# PIC18F44K22_KONTROL_KART.net
KiCad netlist of a schematic drawn in EAGLE
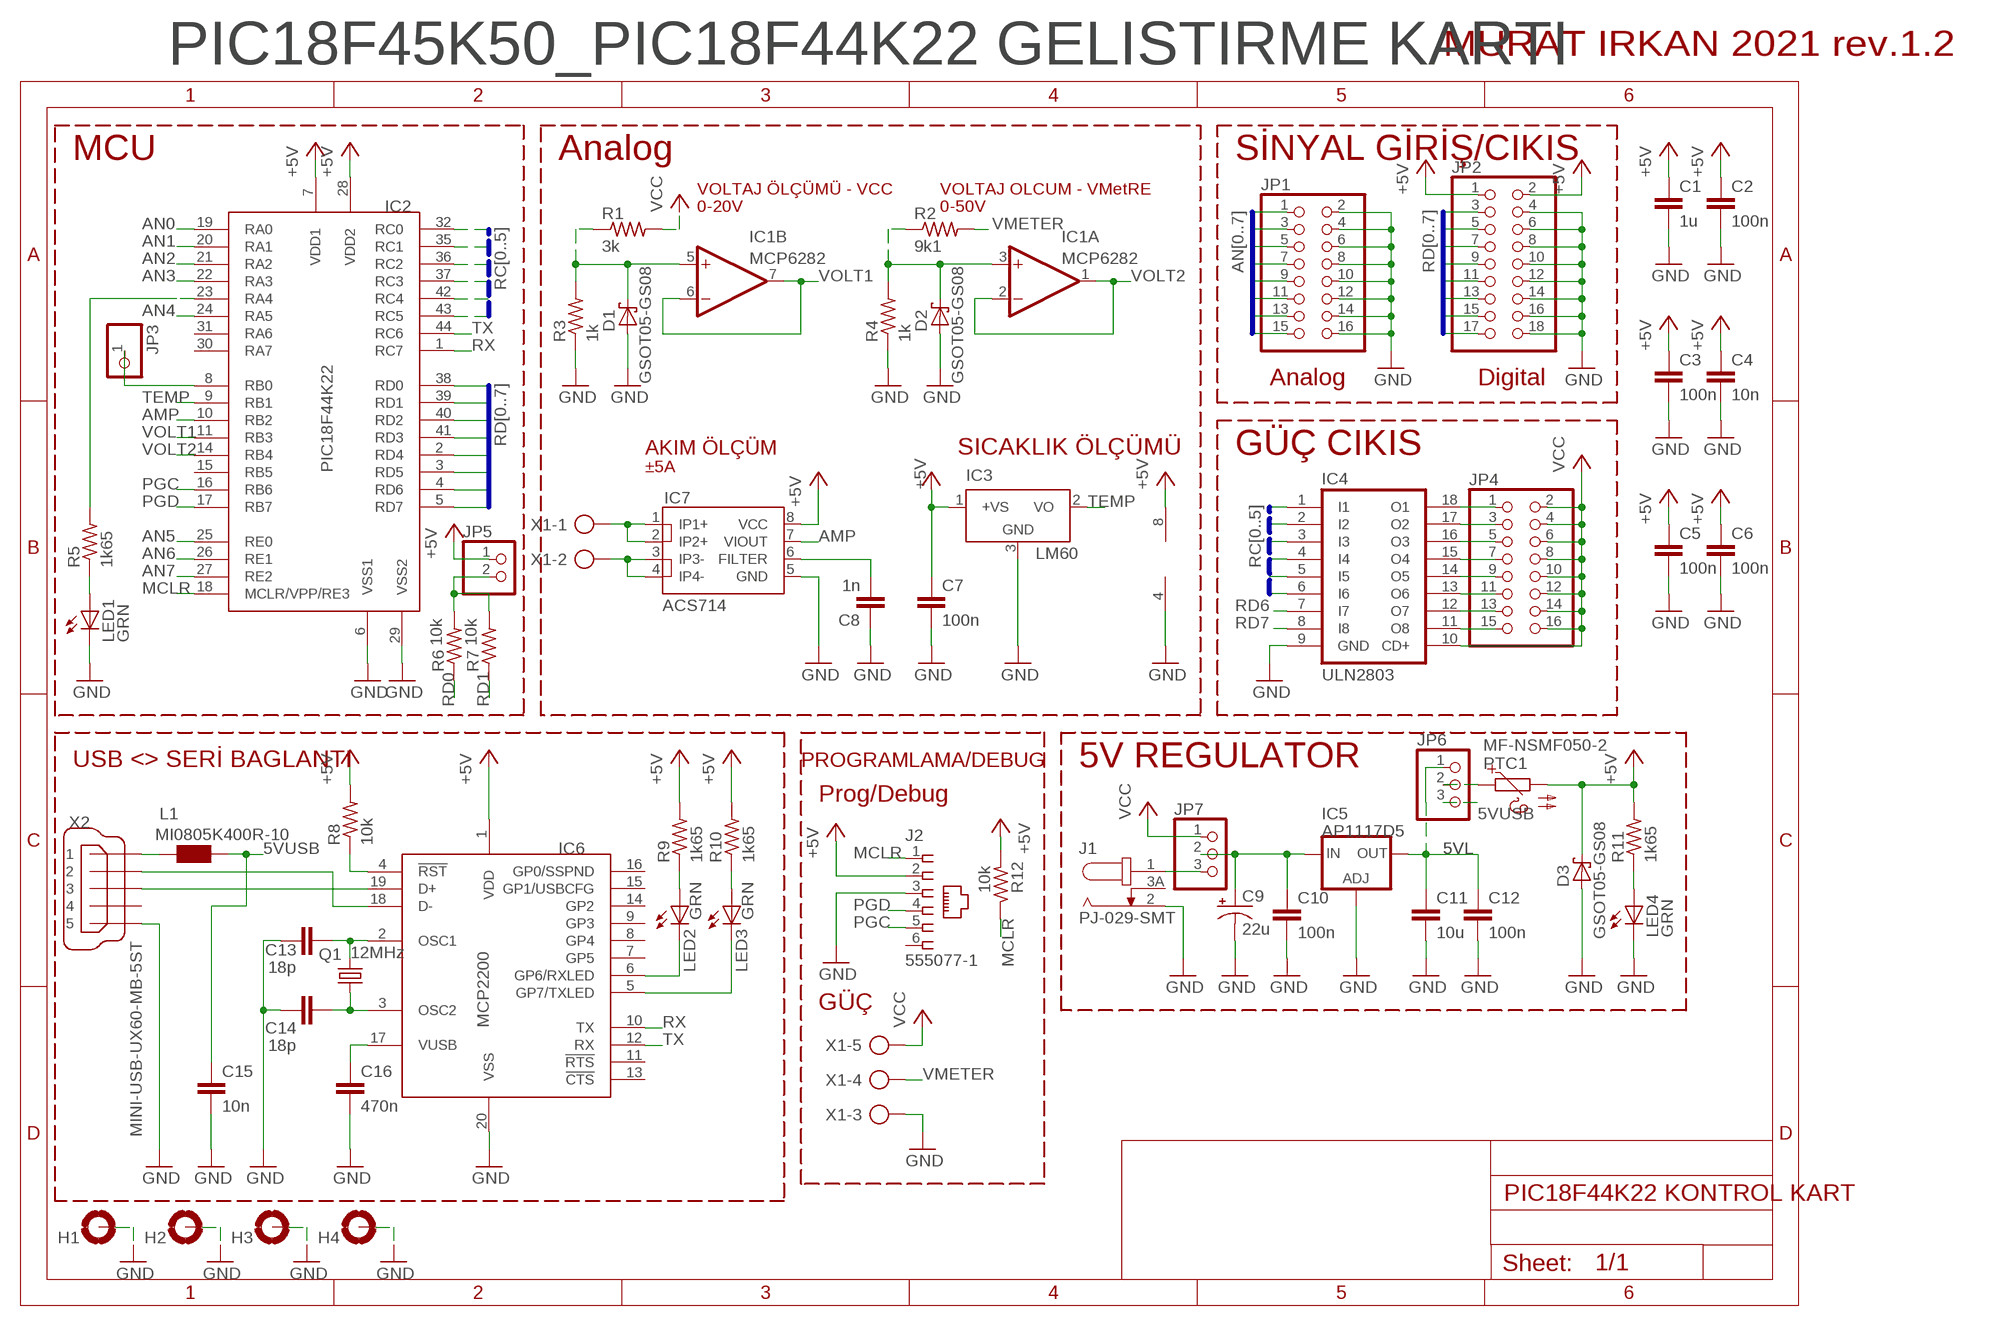
[diagram p0: schematic, sheet 1]

(export (version "E")
  (design (tool "Eeschema 10.0.6"))
  (components
    (comp (ref "C1")
      (value "1u")
      (footprint "eagle-import:C0603")
      (libsource (lib "eagle-import") (part "C-EUC0603"))
    )
    (comp (ref "C2")
      (value "100n")
      (footprint "eagle-import:C0603")
      (libsource (lib "eagle-import") (part "C-EUC0603"))
    )
    (comp (ref "C3")
      (value "100n")
      (footprint "eagle-import:C0603")
      (libsource (lib "eagle-import") (part "C-EUC0603"))
    )
    (comp (ref "C4")
      (value "10n")
      (footprint "eagle-import:C0603")
      (libsource (lib "eagle-import") (part "C-EUC0603"))
    )
    (comp (ref "C5")
      (value "100n")
      (footprint "eagle-import:C0603")
      (libsource (lib "eagle-import") (part "C-EUC0603"))
    )
    (comp (ref "C6")
      (value "100n")
      (footprint "eagle-import:C0603")
      (libsource (lib "eagle-import") (part "C-EUC0603"))
    )
    (comp (ref "C7")
      (value "100n")
      (footprint "eagle-import:C0603")
      (libsource (lib "eagle-import") (part "C-EUC0603"))
    )
    (comp (ref "C8")
      (value "1n")
      (footprint "eagle-import:C0603")
      (libsource (lib "eagle-import") (part "C-EUC0603"))
    )
    (comp (ref "C9")
      (value "22u")
      (footprint "eagle-import:153CLV-0505")
      (libsource (lib "eagle-import") (part "CPOL-US153CLV-0505"))
    )
    (comp (ref "C10")
      (value "100n")
      (footprint "eagle-import:C0603")
      (libsource (lib "eagle-import") (part "C-EUC0603"))
    )
    (comp (ref "C11")
      (value "10u")
      (footprint "eagle-import:C0805")
      (libsource (lib "eagle-import") (part "C-EUC0805"))
    )
    (comp (ref "C12")
      (value "100n")
      (footprint "eagle-import:C0603")
      (libsource (lib "eagle-import") (part "C-EUC0603"))
    )
    (comp (ref "C13")
      (value "18p")
      (footprint "eagle-import:C0603")
      (libsource (lib "eagle-import") (part "C-EUC0603"))
    )
    (comp (ref "C14")
      (value "18p")
      (footprint "eagle-import:C0603")
      (libsource (lib "eagle-import") (part "C-EUC0603"))
    )
    (comp (ref "C15")
      (value "10n")
      (footprint "eagle-import:C0603")
      (libsource (lib "eagle-import") (part "C-EUC0603"))
    )
    (comp (ref "C16")
      (value "470n")
      (footprint "eagle-import:C0603")
      (libsource (lib "eagle-import") (part "C-EUC0603"))
    )
    (comp (ref "D1")
      (value "GSOT05-GS08")
      (footprint "eagle-import:SOT23")
      (libsource (lib "eagle-import") (part "BAS70"))
    )
    (comp (ref "D2")
      (value "GSOT05-GS08")
      (footprint "eagle-import:SOT23")
      (libsource (lib "eagle-import") (part "BAS70"))
    )
    (comp (ref "D3")
      (value "GSOT05-GS08")
      (footprint "eagle-import:SOT23")
      (libsource (lib "eagle-import") (part "BAS70"))
    )
    (comp (ref "H1")
      (value "MOUNT-PAD-ROUND3.2")
      (footprint "eagle-import:3,2-PAD")
      (libsource (lib "eagle-import") (part "MOUNT-PAD-ROUND3.2"))
    )
    (comp (ref "H2")
      (value "MOUNT-PAD-ROUND3.2")
      (footprint "eagle-import:3,2-PAD")
      (libsource (lib "eagle-import") (part "MOUNT-PAD-ROUND3.2"))
    )
    (comp (ref "H3")
      (value "MOUNT-PAD-ROUND3.2")
      (footprint "eagle-import:3,2-PAD")
      (libsource (lib "eagle-import") (part "MOUNT-PAD-ROUND3.2"))
    )
    (comp (ref "H4")
      (value "MOUNT-PAD-ROUND3.2")
      (footprint "eagle-import:3,2-PAD")
      (libsource (lib "eagle-import") (part "MOUNT-PAD-ROUND3.2"))
    )
    (comp (ref "IC1")
      (value "MCP6282")
      (footprint "eagle-import:SO08")
      (libsource (lib "eagle-import") (part "MCP602SN"))
    )
    (comp (ref "IC2")
      (value "PIC18F44K22")
      (footprint "eagle-import:TQFP44")
      (libsource (lib "eagle-import") (part "PIC18F44K22"))
    )
    (comp (ref "IC3")
      (value "LM60")
      (footprint "eagle-import:SOT23")
      (libsource (lib "eagle-import") (part "LM50"))
    )
    (comp (ref "IC4")
      (value "ULN2803")
      (footprint "eagle-import:SO18")
      (libsource (lib "eagle-import") (part "ULN2803"))
    )
    (comp (ref "IC5")
      (value "AP1117D5")
      (footprint "eagle-import:DPACK")
      (libsource (lib "eagle-import") (part "LD117A?DT33TR"))
    )
    (comp (ref "IC6")
      (value "MCP2200")
      (footprint "eagle-import:SSOP20")
      (libsource (lib "eagle-import") (part "MCP2200"))
    )
    (comp (ref "IC7")
      (value "ACS714")
      (footprint "eagle-import:SO08")
      (libsource (lib "eagle-import") (part "ACS712"))
    )
    (comp (ref "J1")
      (value "PJ-029-SMT")
      (footprint "eagle-import:SMT")
      (libsource (lib "eagle-import") (part "PJ-029-SMT"))
    )
    (comp (ref "J2")
      (value "555077-1")
      (footprint "eagle-import:555077-1")
      (libsource (lib "eagle-import") (part "555077-1"))
    )
    (comp (ref "JP1")
      (value "PINHD-2X8")
      (footprint "eagle-import:2X08")
      (libsource (lib "eagle-import") (part "PINHD-2X8"))
    )
    (comp (ref "JP2")
      (value "PINHD-2X9")
      (footprint "eagle-import:2X09")
      (libsource (lib "eagle-import") (part "PINHD-2X9"))
    )
    (comp (ref "JP3")
      (value "PINHD-1X1")
      (footprint "eagle-import:1X01")
      (libsource (lib "eagle-import") (part "PINHD-1X1"))
    )
    (comp (ref "JP4")
      (value "PINHD-2X8")
      (footprint "eagle-import:2X08")
      (libsource (lib "eagle-import") (part "PINHD-2X8"))
    )
    (comp (ref "JP5")
      (value "PINHD-1X2")
      (footprint "eagle-import:1X02")
      (libsource (lib "eagle-import") (part "PINHD-1X2"))
    )
    (comp (ref "JP6")
      (value "PINHD-1X3")
      (footprint "eagle-import:1X03")
      (libsource (lib "eagle-import") (part "PINHD-1X3"))
    )
    (comp (ref "JP7")
      (value "PINHD-1X3")
      (footprint "eagle-import:1X03")
      (libsource (lib "eagle-import") (part "PINHD-1X3"))
    )
    (comp (ref "L1")
      (value "MI0805K400R-10")
      (footprint "eagle-import:0805")
      (libsource (lib "eagle-import") (part "WE-CBF_0805"))
    )
    (comp (ref "LED1")
      (value "GRN")
      (footprint "eagle-import:CHIPLED_0603")
      (libsource (lib "eagle-import") (part "LEDCHIPLED_0603"))
    )
    (comp (ref "LED2")
      (value "GRN")
      (footprint "eagle-import:CHIPLED_0603")
      (libsource (lib "eagle-import") (part "LEDCHIPLED_0603"))
    )
    (comp (ref "LED3")
      (value "GRN")
      (footprint "eagle-import:CHIPLED_0603")
      (libsource (lib "eagle-import") (part "LEDCHIPLED_0603"))
    )
    (comp (ref "LED4")
      (value "GRN")
      (footprint "eagle-import:CHIPLED_0603")
      (libsource (lib "eagle-import") (part "LEDCHIPLED_0603"))
    )
    (comp (ref "PTC1")
      (value "MF-NSMF050-2")
      (footprint "eagle-import:1206")
      (libsource (lib "eagle-import") (part "GENERIC_1206"))
    )
    (comp (ref "Q1")
      (value "12MHz")
      (footprint "eagle-import:HC49UP")
      (libsource (lib "eagle-import") (part "CRYSTALHC49UP"))
    )
    (comp (ref "R1")
      (value "3k")
      (footprint "eagle-import:R0603")
      (libsource (lib "eagle-import") (part "R-US_R0603"))
    )
    (comp (ref "R2")
      (value "9k1")
      (footprint "eagle-import:R0603")
      (libsource (lib "eagle-import") (part "R-US_R0603"))
    )
    (comp (ref "R3")
      (value "1k")
      (footprint "eagle-import:R0603")
      (libsource (lib "eagle-import") (part "R-US_R0603"))
    )
    (comp (ref "R4")
      (value "1k")
      (footprint "eagle-import:R0603")
      (libsource (lib "eagle-import") (part "R-US_R0603"))
    )
    (comp (ref "R5")
      (value "1k65")
      (footprint "eagle-import:R0603")
      (libsource (lib "eagle-import") (part "R-US_R0603"))
    )
    (comp (ref "R6")
      (value "10k")
      (footprint "eagle-import:R0603")
      (libsource (lib "eagle-import") (part "R-US_R0603"))
    )
    (comp (ref "R7")
      (value "10k")
      (footprint "eagle-import:R0603")
      (libsource (lib "eagle-import") (part "R-US_R0603"))
    )
    (comp (ref "R8")
      (value "10k")
      (footprint "eagle-import:R0603")
      (libsource (lib "eagle-import") (part "R-US_R0603"))
    )
    (comp (ref "R9")
      (value "1k65")
      (footprint "eagle-import:R0603")
      (libsource (lib "eagle-import") (part "R-US_R0603"))
    )
    (comp (ref "R10")
      (value "1k65")
      (footprint "eagle-import:R0603")
      (libsource (lib "eagle-import") (part "R-US_R0603"))
    )
    (comp (ref "R11")
      (value "1k65")
      (footprint "eagle-import:R0603")
      (libsource (lib "eagle-import") (part "R-US_R0603"))
    )
    (comp (ref "R12")
      (value "10k")
      (footprint "eagle-import:R0603")
      (libsource (lib "eagle-import") (part "R-US_R0603"))
    )
    (comp (ref "X1")
      (value "OSTTE-5")
      (footprint "eagle-import:OSTTE-5")
      (libsource (lib "eagle-import") (part "OSTTE-5"))
    )
    (comp (ref "X2")
      (value "MINI-USB-UX60-MB-5ST")
      (footprint "eagle-import:UX60-MB-5ST")
      (libsource (lib "eagle-import") (part "MINI-USB-UX60-MB-5ST"))
    )
  )
  (nets
    (net (code "1") (name "+5V") (class "Default")
      (node (ref "C1") (pin "1") (pinfunction "1_1") (pintype "passive"))
      (node (ref "C2") (pin "1") (pinfunction "1_1") (pintype "passive"))
      (node (ref "C3") (pin "1") (pinfunction "1_1") (pintype "passive"))
      (node (ref "C4") (pin "1") (pinfunction "1_1") (pintype "passive"))
      (node (ref "C5") (pin "1") (pinfunction "1_1") (pintype "passive"))
      (node (ref "C6") (pin "1") (pinfunction "1_1") (pintype "passive"))
      (node (ref "C7") (pin "1") (pinfunction "1_1") (pintype "passive"))
      (node (ref "D3") (pin "3") (pinfunction "C_3") (pintype "passive"))
      (node (ref "IC1") (pin "8") (pinfunction "V+_8") (pintype "power_in"))
      (node (ref "IC2") (pin "28") (pinfunction "VDD2_28") (pintype "power_in"))
      (node (ref "IC2") (pin "7") (pinfunction "VDD1_7") (pintype "power_in"))
      (node (ref "IC3") (pin "1") (pinfunction "+VS_1") (pintype "input"))
      (node (ref "IC6") (pin "1") (pinfunction "VDD_1") (pintype "bidirectional"))
      (node (ref "IC7") (pin "8") (pinfunction "VCC_8") (pintype "power_in"))
      (node (ref "J2") (pin "2") (pinfunction "2_2") (pintype "passive"))
      (node (ref "JP2") (pin "1") (pinfunction "1_1") (pintype "passive"))
      (node (ref "JP2") (pin "2") (pinfunction "2_2") (pintype "passive"))
      (node (ref "JP5") (pin "1") (pinfunction "1_1") (pintype "passive"))
      (node (ref "PTC1") (pin "2") (pinfunction "2_2") (pintype "passive"))
      (node (ref "R10") (pin "2") (pinfunction "2_2") (pintype "passive"))
      (node (ref "R11") (pin "2") (pinfunction "2_2") (pintype "passive"))
      (node (ref "R12") (pin "2") (pinfunction "2_2") (pintype "passive"))
      (node (ref "R8") (pin "2") (pinfunction "2_2") (pintype "passive"))
      (node (ref "R9") (pin "2") (pinfunction "2_2") (pintype "passive"))
    )
    (net (code "2") (name "/5VL") (class "Default")
      (node (ref "C11") (pin "1") (pinfunction "1_1") (pintype "passive"))
      (node (ref "C12") (pin "1") (pinfunction "1_1") (pintype "passive"))
      (node (ref "IC5") (pin "4") (pinfunction "OUT_4") (pintype "passive"))
      (node (ref "JP6") (pin "1") (pinfunction "1_1") (pintype "passive"))
    )
    (net (code "3") (name "/5VUSB") (class "Default")
      (node (ref "C15") (pin "1") (pinfunction "1_1") (pintype "passive"))
      (node (ref "JP6") (pin "3") (pinfunction "3_3") (pintype "passive"))
      (node (ref "L1") (pin "1") (pinfunction "1_1") (pintype "passive"))
    )
    (net (code "4") (name "/AMP") (class "Default")
      (node (ref "IC2") (pin "10") (pinfunction "RB2_10") (pintype "bidirectional"))
      (node (ref "IC7") (pin "7") (pinfunction "VIOUT_7") (pintype "output"))
    )
    (net (code "5") (name "/AN0") (class "Default")
      (node (ref "IC2") (pin "19") (pinfunction "RA0_19") (pintype "bidirectional"))
      (node (ref "JP1") (pin "15") (pinfunction "15_15") (pintype "passive"))
    )
    (net (code "6") (name "/AN1") (class "Default")
      (node (ref "IC2") (pin "20") (pinfunction "RA1_20") (pintype "bidirectional"))
      (node (ref "JP1") (pin "13") (pinfunction "13_13") (pintype "passive"))
    )
    (net (code "7") (name "/AN2") (class "Default")
      (node (ref "IC2") (pin "21") (pinfunction "RA2_21") (pintype "bidirectional"))
      (node (ref "JP1") (pin "11") (pinfunction "11_11") (pintype "passive"))
    )
    (net (code "8") (name "/AN3") (class "Default")
      (node (ref "IC2") (pin "22") (pinfunction "RA3_22") (pintype "bidirectional"))
      (node (ref "JP1") (pin "9") (pinfunction "9_9") (pintype "passive"))
    )
    (net (code "9") (name "/AN4") (class "Default")
      (node (ref "IC2") (pin "24") (pinfunction "RA5_24") (pintype "bidirectional"))
      (node (ref "JP1") (pin "7") (pinfunction "7_7") (pintype "passive"))
    )
    (net (code "10") (name "/AN5") (class "Default")
      (node (ref "IC2") (pin "25") (pinfunction "RE0_25") (pintype "bidirectional"))
      (node (ref "JP1") (pin "5") (pinfunction "5_5") (pintype "passive"))
    )
    (net (code "11") (name "/AN6") (class "Default")
      (node (ref "IC2") (pin "26") (pinfunction "RE1_26") (pintype "bidirectional"))
      (node (ref "JP1") (pin "3") (pinfunction "3_3") (pintype "passive"))
    )
    (net (code "12") (name "/AN7") (class "Default")
      (node (ref "IC2") (pin "27") (pinfunction "RE2_27") (pintype "bidirectional"))
      (node (ref "JP1") (pin "1") (pinfunction "1_1") (pintype "passive"))
    )
    (net (code "14") (name "/MCLR") (class "Default")
      (node (ref "IC2") (pin "18") (pinfunction "MCLR/VPP/RE3_18") (pintype "bidirectional"))
      (node (ref "J2") (pin "1") (pinfunction "1_1") (pintype "passive"))
      (node (ref "R12") (pin "1") (pinfunction "1_1") (pintype "passive"))
    )
    (net (code "15") (name "/PGC") (class "Default")
      (node (ref "IC2") (pin "16") (pinfunction "RB6_16") (pintype "bidirectional"))
      (node (ref "J2") (pin "5") (pinfunction "5_5") (pintype "passive"))
    )
    (net (code "16") (name "/PGD") (class "Default")
      (node (ref "IC2") (pin "17") (pinfunction "RB7_17") (pintype "bidirectional"))
      (node (ref "J2") (pin "4") (pinfunction "4_4") (pintype "passive"))
    )
    (net (code "17") (name "/RC0") (class "Default")
      (node (ref "IC2") (pin "32") (pinfunction "RC0_32") (pintype "bidirectional"))
      (node (ref "IC4") (pin "6") (pinfunction "I6_6") (pintype "input"))
    )
    (net (code "18") (name "/RC1") (class "Default")
      (node (ref "IC2") (pin "35") (pinfunction "RC1_35") (pintype "bidirectional"))
      (node (ref "IC4") (pin "5") (pinfunction "I5_5") (pintype "input"))
    )
    (net (code "19") (name "/RC2") (class "Default")
      (node (ref "IC2") (pin "36") (pinfunction "RC2_36") (pintype "bidirectional"))
      (node (ref "IC4") (pin "4") (pinfunction "I4_4") (pintype "input"))
    )
    (net (code "20") (name "/RC3") (class "Default")
      (node (ref "IC2") (pin "37") (pinfunction "RC3_37") (pintype "bidirectional"))
      (node (ref "IC4") (pin "3") (pinfunction "I3_3") (pintype "input"))
    )
    (net (code "21") (name "/RC4") (class "Default")
      (node (ref "IC2") (pin "42") (pinfunction "RC4_42") (pintype "bidirectional"))
      (node (ref "IC4") (pin "2") (pinfunction "I2_2") (pintype "input"))
    )
    (net (code "22") (name "/RC5") (class "Default")
      (node (ref "IC2") (pin "43") (pinfunction "RC5_43") (pintype "bidirectional"))
      (node (ref "IC4") (pin "1") (pinfunction "I1_1") (pintype "input"))
    )
    (net (code "24") (name "/RD0") (class "Default")
      (node (ref "IC2") (pin "38") (pinfunction "RD0_38") (pintype "bidirectional"))
      (node (ref "JP2") (pin "17") (pinfunction "17_17") (pintype "passive"))
      (node (ref "R6") (pin "1") (pinfunction "1_1") (pintype "passive"))
    )
    (net (code "25") (name "/RD1") (class "Default")
      (node (ref "IC2") (pin "39") (pinfunction "RD1_39") (pintype "bidirectional"))
      (node (ref "JP2") (pin "15") (pinfunction "15_15") (pintype "passive"))
      (node (ref "R7") (pin "1") (pinfunction "1_1") (pintype "passive"))
    )
    (net (code "26") (name "/RD2") (class "Default")
      (node (ref "IC2") (pin "40") (pinfunction "RD2_40") (pintype "bidirectional"))
      (node (ref "JP2") (pin "13") (pinfunction "13_13") (pintype "passive"))
    )
    (net (code "27") (name "/RD3") (class "Default")
      (node (ref "IC2") (pin "41") (pinfunction "RD3_41") (pintype "bidirectional"))
      (node (ref "JP2") (pin "11") (pinfunction "11_11") (pintype "passive"))
    )
    (net (code "28") (name "/RD4") (class "Default")
      (node (ref "IC2") (pin "2") (pinfunction "RD4_2") (pintype "bidirectional"))
      (node (ref "JP2") (pin "9") (pinfunction "9_9") (pintype "passive"))
    )
    (net (code "29") (name "/RD5") (class "Default")
      (node (ref "IC2") (pin "3") (pinfunction "RD5_3") (pintype "bidirectional"))
      (node (ref "JP2") (pin "7") (pinfunction "7_7") (pintype "passive"))
    )
    (net (code "30") (name "/RD6") (class "Default")
      (node (ref "IC2") (pin "4") (pinfunction "RD6_4") (pintype "bidirectional"))
      (node (ref "IC4") (pin "7") (pinfunction "I7_7") (pintype "input"))
      (node (ref "JP2") (pin "5") (pinfunction "5_5") (pintype "passive"))
    )
    (net (code "31") (name "/RD7") (class "Default")
      (node (ref "IC2") (pin "5") (pinfunction "RD7_5") (pintype "bidirectional"))
      (node (ref "IC4") (pin "8") (pinfunction "I8_8") (pintype "input"))
      (node (ref "JP2") (pin "3") (pinfunction "3_3") (pintype "passive"))
    )
    (net (code "33") (name "/RX") (class "Default")
      (node (ref "IC2") (pin "1") (pinfunction "RC7_1") (pintype "bidirectional"))
      (node (ref "IC6") (pin "10") (pinfunction "TX_10") (pintype "bidirectional"))
    )
    (net (code "34") (name "/TEMP") (class "Default")
      (node (ref "IC2") (pin "9") (pinfunction "RB1_9") (pintype "bidirectional"))
      (node (ref "IC3") (pin "2") (pinfunction "VO_2") (pintype "input"))
    )
    (net (code "35") (name "/TX") (class "Default")
      (node (ref "IC2") (pin "44") (pinfunction "RC6_44") (pintype "bidirectional"))
      (node (ref "IC6") (pin "12") (pinfunction "RX_12") (pintype "bidirectional"))
    )
    (net (code "36") (name "/VMETER") (class "Default")
      (node (ref "R2") (pin "2") (pinfunction "2_2") (pintype "passive"))
      (node (ref "X1") (pin "4") (pinfunction "KL_4") (pintype "passive"))
    )
    (net (code "37") (name "/VOLT1") (class "Default")
      (node (ref "IC1") (pin "6") (pinfunction "-IN_6") (pintype "input"))
      (node (ref "IC1") (pin "7") (pinfunction "OUT_7") (pintype "output"))
      (node (ref "IC2") (pin "11") (pinfunction "RB3_11") (pintype "bidirectional"))
    )
    (net (code "38") (name "/VOLT2") (class "Default")
      (node (ref "IC1") (pin "1") (pinfunction "OUT_1") (pintype "output"))
      (node (ref "IC1") (pin "2") (pinfunction "-IN_2") (pintype "input"))
      (node (ref "IC2") (pin "14") (pinfunction "RB4_14") (pintype "bidirectional"))
    )
    (net (code "39") (name "GND") (class "Default")
      (node (ref "C1") (pin "2") (pinfunction "2_2") (pintype "passive"))
      (node (ref "C10") (pin "2") (pinfunction "2_2") (pintype "passive"))
      (node (ref "C11") (pin "2") (pinfunction "2_2") (pintype "passive"))
      (node (ref "C12") (pin "2") (pinfunction "2_2") (pintype "passive"))
      (node (ref "C13") (pin "1") (pinfunction "1_1") (pintype "passive"))
      (node (ref "C14") (pin "1") (pinfunction "1_1") (pintype "passive"))
      (node (ref "C15") (pin "2") (pinfunction "2_2") (pintype "passive"))
      (node (ref "C16") (pin "2") (pinfunction "2_2") (pintype "passive"))
      (node (ref "C2") (pin "2") (pinfunction "2_2") (pintype "passive"))
      (node (ref "C3") (pin "2") (pinfunction "2_2") (pintype "passive"))
      (node (ref "C4") (pin "2") (pinfunction "2_2") (pintype "passive"))
      (node (ref "C5") (pin "2") (pinfunction "2_2") (pintype "passive"))
      (node (ref "C6") (pin "2") (pinfunction "2_2") (pintype "passive"))
      (node (ref "C7") (pin "2") (pinfunction "2_2") (pintype "passive"))
      (node (ref "C8") (pin "1") (pinfunction "1_1") (pintype "passive"))
      (node (ref "C9") (pin "-") (pinfunction "-_-") (pintype "passive"))
      (node (ref "D1") (pin "1") (pinfunction "A_1") (pintype "passive"))
      (node (ref "D2") (pin "1") (pinfunction "A_1") (pintype "passive"))
      (node (ref "D3") (pin "1") (pinfunction "A_1") (pintype "passive"))
      (node (ref "H1") (pin "B3,2") (pinfunction "MOUNT_B3,2") (pintype "passive"))
      (node (ref "H2") (pin "B3,2") (pinfunction "MOUNT_B3,2") (pintype "passive"))
      (node (ref "H3") (pin "B3,2") (pinfunction "MOUNT_B3,2") (pintype "passive"))
      (node (ref "H4") (pin "B3,2") (pinfunction "MOUNT_B3,2") (pintype "passive"))
      (node (ref "IC1") (pin "4") (pinfunction "V-_4") (pintype "power_in"))
      (node (ref "IC2") (pin "29") (pinfunction "VSS2_29") (pintype "power_in"))
      (node (ref "IC2") (pin "6") (pinfunction "VSS1_6") (pintype "power_in"))
      (node (ref "IC3") (pin "3") (pinfunction "GND_3") (pintype "power_in"))
      (node (ref "IC4") (pin "9") (pinfunction "GND_9") (pintype "power_in"))
      (node (ref "IC5") (pin "1") (pinfunction "ADJ_1") (pintype "input"))
      (node (ref "IC6") (pin "20") (pinfunction "VSS_20") (pintype "bidirectional"))
      (node (ref "IC7") (pin "5") (pinfunction "GND_5") (pintype "power_in"))
      (node (ref "J1") (pin "2") (pinfunction "1_2") (pintype "passive"))
      (node (ref "J2") (pin "3") (pinfunction "3_3") (pintype "passive"))
      (node (ref "JP1") (pin "10") (pinfunction "10_10") (pintype "passive"))
      (node (ref "JP1") (pin "12") (pinfunction "12_12") (pintype "passive"))
      (node (ref "JP1") (pin "14") (pinfunction "14_14") (pintype "passive"))
      (node (ref "JP1") (pin "16") (pinfunction "16_16") (pintype "passive"))
      (node (ref "JP1") (pin "2") (pinfunction "2_2") (pintype "passive"))
      (node (ref "JP1") (pin "4") (pinfunction "4_4") (pintype "passive"))
      (node (ref "JP1") (pin "6") (pinfunction "6_6") (pintype "passive"))
      (node (ref "JP1") (pin "8") (pinfunction "8_8") (pintype "passive"))
      (node (ref "JP2") (pin "10") (pinfunction "10_10") (pintype "passive"))
      (node (ref "JP2") (pin "12") (pinfunction "12_12") (pintype "passive"))
      (node (ref "JP2") (pin "14") (pinfunction "14_14") (pintype "passive"))
      (node (ref "JP2") (pin "16") (pinfunction "16_16") (pintype "passive"))
      (node (ref "JP2") (pin "18") (pinfunction "18_18") (pintype "passive"))
      (node (ref "JP2") (pin "4") (pinfunction "4_4") (pintype "passive"))
      (node (ref "JP2") (pin "6") (pinfunction "6_6") (pintype "passive"))
      (node (ref "JP2") (pin "8") (pinfunction "8_8") (pintype "passive"))
      (node (ref "LED1") (pin "C") (pinfunction "C_C") (pintype "passive"))
      (node (ref "LED4") (pin "C") (pinfunction "C_C") (pintype "passive"))
      (node (ref "R3") (pin "1") (pinfunction "1_1") (pintype "passive"))
      (node (ref "R4") (pin "1") (pinfunction "1_1") (pintype "passive"))
      (node (ref "X1") (pin "3") (pinfunction "KL_3") (pintype "passive"))
      (node (ref "X2") (pin "5") (pinfunction "5_5") (pintype "input"))
    )
    (net (code "40") (name "Net-(D1-C)") (class "Default")
      (node (ref "D1") (pin "3") (pinfunction "C_3") (pintype "passive"))
      (node (ref "IC1") (pin "5") (pinfunction "+IN_5") (pintype "input"))
      (node (ref "R1") (pin "1") (pinfunction "1_1") (pintype "passive"))
      (node (ref "R3") (pin "2") (pinfunction "2_2") (pintype "passive"))
    )
    (net (code "41") (name "Net-(D2-C)") (class "Default")
      (node (ref "D2") (pin "3") (pinfunction "C_3") (pintype "passive"))
      (node (ref "IC1") (pin "3") (pinfunction "+IN_3") (pintype "input"))
      (node (ref "R2") (pin "1") (pinfunction "1_1") (pintype "passive"))
      (node (ref "R4") (pin "2") (pinfunction "2_2") (pintype "passive"))
    )
    (net (code "42") (name "Net-(IC2-RA4)") (class "Default")
      (node (ref "IC2") (pin "23") (pinfunction "RA4_23") (pintype "bidirectional"))
      (node (ref "R5") (pin "2") (pinfunction "2_2") (pintype "passive"))
    )
    (net (code "43") (name "Net-(IC2-RB0)") (class "Default")
      (node (ref "IC2") (pin "8") (pinfunction "RB0_8") (pintype "bidirectional"))
      (node (ref "JP3") (pin "1") (pinfunction "1_1") (pintype "passive"))
    )
    (net (code "44") (name "Net-(IC4-O1)") (class "Default")
      (node (ref "IC4") (pin "18") (pinfunction "O1_18") (pintype "open_collector"))
      (node (ref "JP4") (pin "1") (pinfunction "1_1") (pintype "passive"))
    )
    (net (code "45") (name "Net-(IC4-O2)") (class "Default")
      (node (ref "IC4") (pin "17") (pinfunction "O2_17") (pintype "open_collector"))
      (node (ref "JP4") (pin "3") (pinfunction "3_3") (pintype "passive"))
    )
    (net (code "46") (name "Net-(IC4-O3)") (class "Default")
      (node (ref "IC4") (pin "16") (pinfunction "O3_16") (pintype "open_collector"))
      (node (ref "JP4") (pin "5") (pinfunction "5_5") (pintype "passive"))
    )
    (net (code "47") (name "Net-(IC4-O4)") (class "Default")
      (node (ref "IC4") (pin "15") (pinfunction "O4_15") (pintype "open_collector"))
      (node (ref "JP4") (pin "7") (pinfunction "7_7") (pintype "passive"))
    )
    (net (code "48") (name "Net-(IC4-O5)") (class "Default")
      (node (ref "IC4") (pin "14") (pinfunction "O5_14") (pintype "open_collector"))
      (node (ref "JP4") (pin "9") (pinfunction "9_9") (pintype "passive"))
    )
    (net (code "49") (name "Net-(IC4-O6)") (class "Default")
      (node (ref "IC4") (pin "13") (pinfunction "O6_13") (pintype "open_collector"))
      (node (ref "JP4") (pin "11") (pinfunction "11_11") (pintype "passive"))
    )
    (net (code "50") (name "Net-(IC4-O7)") (class "Default")
      (node (ref "IC4") (pin "12") (pinfunction "O7_12") (pintype "open_collector"))
      (node (ref "JP4") (pin "13") (pinfunction "13_13") (pintype "passive"))
    )
    (net (code "51") (name "Net-(IC4-O8)") (class "Default")
      (node (ref "IC4") (pin "11") (pinfunction "O8_11") (pintype "open_collector"))
      (node (ref "JP4") (pin "15") (pinfunction "15_15") (pintype "passive"))
    )
    (net (code "52") (name "Net-(IC5-IN)") (class "Default")
      (node (ref "C10") (pin "1") (pinfunction "1_1") (pintype "passive"))
      (node (ref "C9") (pin "+") (pinfunction "+_+") (pintype "passive"))
      (node (ref "IC5") (pin "3") (pinfunction "IN_3") (pintype "input"))
      (node (ref "JP7") (pin "2") (pinfunction "2_2") (pintype "passive"))
    )
    (net (code "53") (name "Net-(IC6-D+)") (class "Default")
      (node (ref "IC6") (pin "19") (pinfunction "D+_19") (pintype "bidirectional"))
      (node (ref "X2") (pin "3") (pinfunction "3_3") (pintype "input"))
    )
    (net (code "54") (name "Net-(IC6-D-)") (class "Default")
      (node (ref "IC6") (pin "18") (pinfunction "D-_18") (pintype "bidirectional"))
      (node (ref "X2") (pin "2") (pinfunction "2_2") (pintype "input"))
    )
    (net (code "55") (name "Net-(IC6-GP6{slash}RXLED)") (class "Default")
      (node (ref "IC6") (pin "6") (pinfunction "GP6/RXLED_6") (pintype "bidirectional"))
      (node (ref "LED2") (pin "C") (pinfunction "C_C") (pintype "passive"))
    )
    (net (code "56") (name "Net-(IC6-GP7{slash}TXLED)") (class "Default")
      (node (ref "IC6") (pin "5") (pinfunction "GP7/TXLED_5") (pintype "bidirectional"))
      (node (ref "LED3") (pin "C") (pinfunction "C_C") (pintype "passive"))
    )
    (net (code "57") (name "Net-(IC6-OSC1)") (class "Default")
      (node (ref "C13") (pin "2") (pinfunction "2_2") (pintype "passive"))
      (node (ref "IC6") (pin "2") (pinfunction "OSC1_2") (pintype "bidirectional"))
      (node (ref "Q1") (pin "2") (pinfunction "2_2") (pintype "passive"))
    )
    (net (code "58") (name "Net-(IC6-OSC2)") (class "Default")
      (node (ref "C14") (pin "2") (pinfunction "2_2") (pintype "passive"))
      (node (ref "IC6") (pin "3") (pinfunction "OSC2_3") (pintype "bidirectional"))
      (node (ref "Q1") (pin "1") (pinfunction "1_1") (pintype "passive"))
    )
    (net (code "59") (name "Net-(IC6-VUSB)") (class "Default")
      (node (ref "C16") (pin "1") (pinfunction "1_1") (pintype "passive"))
      (node (ref "IC6") (pin "17") (pinfunction "VUSB_17") (pintype "bidirectional"))
    )
    (net (code "60") (name "Net-(IC6-~{RST})") (class "Default")
      (node (ref "IC6") (pin "4") (pinfunction "~{RST}_4") (pintype "bidirectional"))
      (node (ref "R8") (pin "1") (pinfunction "1_1") (pintype "passive"))
    )
    (net (code "61") (name "Net-(IC7-FILTER)") (class "Default")
      (node (ref "C8") (pin "2") (pinfunction "2_2") (pintype "passive"))
      (node (ref "IC7") (pin "6") (pinfunction "FILTER_6") (pintype "passive"))
    )
    (net (code "62") (name "Net-(IC7-IP1+)") (class "Default")
      (node (ref "IC7") (pin "1") (pinfunction "IP1+_1") (pintype "bidirectional"))
      (node (ref "IC7") (pin "2") (pinfunction "IP2+_2") (pintype "bidirectional"))
      (node (ref "X1") (pin "1") (pinfunction "KL_1") (pintype "passive"))
    )
    (net (code "63") (name "Net-(IC7-IP3-)") (class "Default")
      (node (ref "IC7") (pin "3") (pinfunction "IP3-_3") (pintype "bidirectional"))
      (node (ref "IC7") (pin "4") (pinfunction "IP4-_4") (pintype "bidirectional"))
      (node (ref "X1") (pin "2") (pinfunction "KL_2") (pintype "passive"))
    )
    (net (code "64") (name "Net-(J1-3)") (class "Default")
      (node (ref "J1") (pin "1") (pinfunction "3_1") (pintype "passive"))
      (node (ref "JP7") (pin "3") (pinfunction "3_3") (pintype "passive"))
    )
    (net (code "65") (name "Net-(JP5-Pad2)") (class "Default")
      (node (ref "JP5") (pin "2") (pinfunction "2_2") (pintype "passive"))
      (node (ref "R6") (pin "2") (pinfunction "2_2") (pintype "passive"))
      (node (ref "R7") (pin "2") (pinfunction "2_2") (pintype "passive"))
    )
    (net (code "66") (name "Net-(JP6-Pad2)") (class "Default")
      (node (ref "JP6") (pin "2") (pinfunction "2_2") (pintype "passive"))
      (node (ref "PTC1") (pin "1") (pinfunction "1_1") (pintype "passive"))
    )
    (net (code "67") (name "Net-(L1-Pad2)") (class "Default")
      (node (ref "L1") (pin "2") (pinfunction "2_2") (pintype "passive"))
      (node (ref "X2") (pin "1") (pinfunction "1_1") (pintype "input"))
    )
    (net (code "68") (name "Net-(LED1-PadA)") (class "Default")
      (node (ref "LED1") (pin "A") (pinfunction "A_A") (pintype "passive"))
      (node (ref "R5") (pin "1") (pinfunction "1_1") (pintype "passive"))
    )
    (net (code "69") (name "Net-(LED2-PadA)") (class "Default")
      (node (ref "LED2") (pin "A") (pinfunction "A_A") (pintype "passive"))
      (node (ref "R9") (pin "1") (pinfunction "1_1") (pintype "passive"))
    )
    (net (code "70") (name "Net-(LED3-PadA)") (class "Default")
      (node (ref "LED3") (pin "A") (pinfunction "A_A") (pintype "passive"))
      (node (ref "R10") (pin "1") (pinfunction "1_1") (pintype "passive"))
    )
    (net (code "71") (name "Net-(LED4-PadA)") (class "Default")
      (node (ref "LED4") (pin "A") (pinfunction "A_A") (pintype "passive"))
      (node (ref "R11") (pin "1") (pinfunction "1_1") (pintype "passive"))
    )
    (net (code "72") (name "VCC") (class "Default")
      (node (ref "IC4") (pin "10") (pinfunction "CD+_10") (pintype "passive"))
      (node (ref "JP4") (pin "10") (pinfunction "10_10") (pintype "passive"))
      (node (ref "JP4") (pin "12") (pinfunction "12_12") (pintype "passive"))
      (node (ref "JP4") (pin "14") (pinfunction "14_14") (pintype "passive"))
      (node (ref "JP4") (pin "16") (pinfunction "16_16") (pintype "passive"))
      (node (ref "JP4") (pin "2") (pinfunction "2_2") (pintype "passive"))
      (node (ref "JP4") (pin "4") (pinfunction "4_4") (pintype "passive"))
      (node (ref "JP4") (pin "6") (pinfunction "6_6") (pintype "passive"))
      (node (ref "JP4") (pin "8") (pinfunction "8_8") (pintype "passive"))
      (node (ref "JP7") (pin "1") (pinfunction "1_1") (pintype "passive"))
      (node (ref "R1") (pin "2") (pinfunction "2_2") (pintype "passive"))
      (node (ref "X1") (pin "5") (pinfunction "KL_5") (pintype "passive"))
    )
    (net (code "73") (name "unconnected-(IC2-RA6-Pad31)") (class "Default")
      (node (ref "IC2") (pin "31") (pinfunction "RA6_31") (pintype "bidirectional"))
    )
    (net (code "74") (name "unconnected-(IC2-RA7-Pad30)") (class "Default")
      (node (ref "IC2") (pin "30") (pinfunction "RA7_30") (pintype "bidirectional"))
    )
    (net (code "75") (name "unconnected-(IC2-RB5-Pad15)") (class "Default")
      (node (ref "IC2") (pin "15") (pinfunction "RB5_15") (pintype "bidirectional"))
    )
    (net (code "76") (name "unconnected-(IC6-GP0{slash}SSPND-Pad16)") (class "Default")
      (node (ref "IC6") (pin "16") (pinfunction "GP0/SSPND_16") (pintype "bidirectional"))
    )
    (net (code "77") (name "unconnected-(IC6-GP1{slash}USBCFG-Pad15)") (class "Default")
      (node (ref "IC6") (pin "15") (pinfunction "GP1/USBCFG_15") (pintype "bidirectional"))
    )
    (net (code "78") (name "unconnected-(IC6-GP2-Pad14)") (class "Default")
      (node (ref "IC6") (pin "14") (pinfunction "GP2_14") (pintype "bidirectional"))
    )
    (net (code "79") (name "unconnected-(IC6-GP3-Pad9)") (class "Default")
      (node (ref "IC6") (pin "9") (pinfunction "GP3_9") (pintype "bidirectional"))
    )
    (net (code "80") (name "unconnected-(IC6-GP4-Pad8)") (class "Default")
      (node (ref "IC6") (pin "8") (pinfunction "GP4_8") (pintype "bidirectional"))
    )
    (net (code "81") (name "unconnected-(IC6-GP5-Pad7)") (class "Default")
      (node (ref "IC6") (pin "7") (pinfunction "GP5_7") (pintype "bidirectional"))
    )
    (net (code "82") (name "unconnected-(IC6-~{CTS}-Pad13)") (class "Default")
      (node (ref "IC6") (pin "13") (pinfunction "~{CTS}_13") (pintype "bidirectional"))
    )
    (net (code "83") (name "unconnected-(IC6-~{RTS}-Pad11)") (class "Default")
      (node (ref "IC6") (pin "11") (pinfunction "~{RTS}_11") (pintype "bidirectional"))
    )
    (net (code "84") (name "unconnected-(J1-2-Pad3A)") (class "Default")
      (node (ref "J1") (pin "3A") (pinfunction "2_3A") (pintype "passive"))
    )
    (net (code "85") (name "unconnected-(J2-Pad6)") (class "Default")
      (node (ref "J2") (pin "6") (pinfunction "6_6") (pintype "passive"))
    )
    (net (code "86") (name "unconnected-(X2-Pad4)") (class "Default")
      (node (ref "X2") (pin "4") (pinfunction "4_4") (pintype "input"))
    )
  )
)
